# Laser-Driver.net
KiCad netlist of a schematic drawn in EAGLE
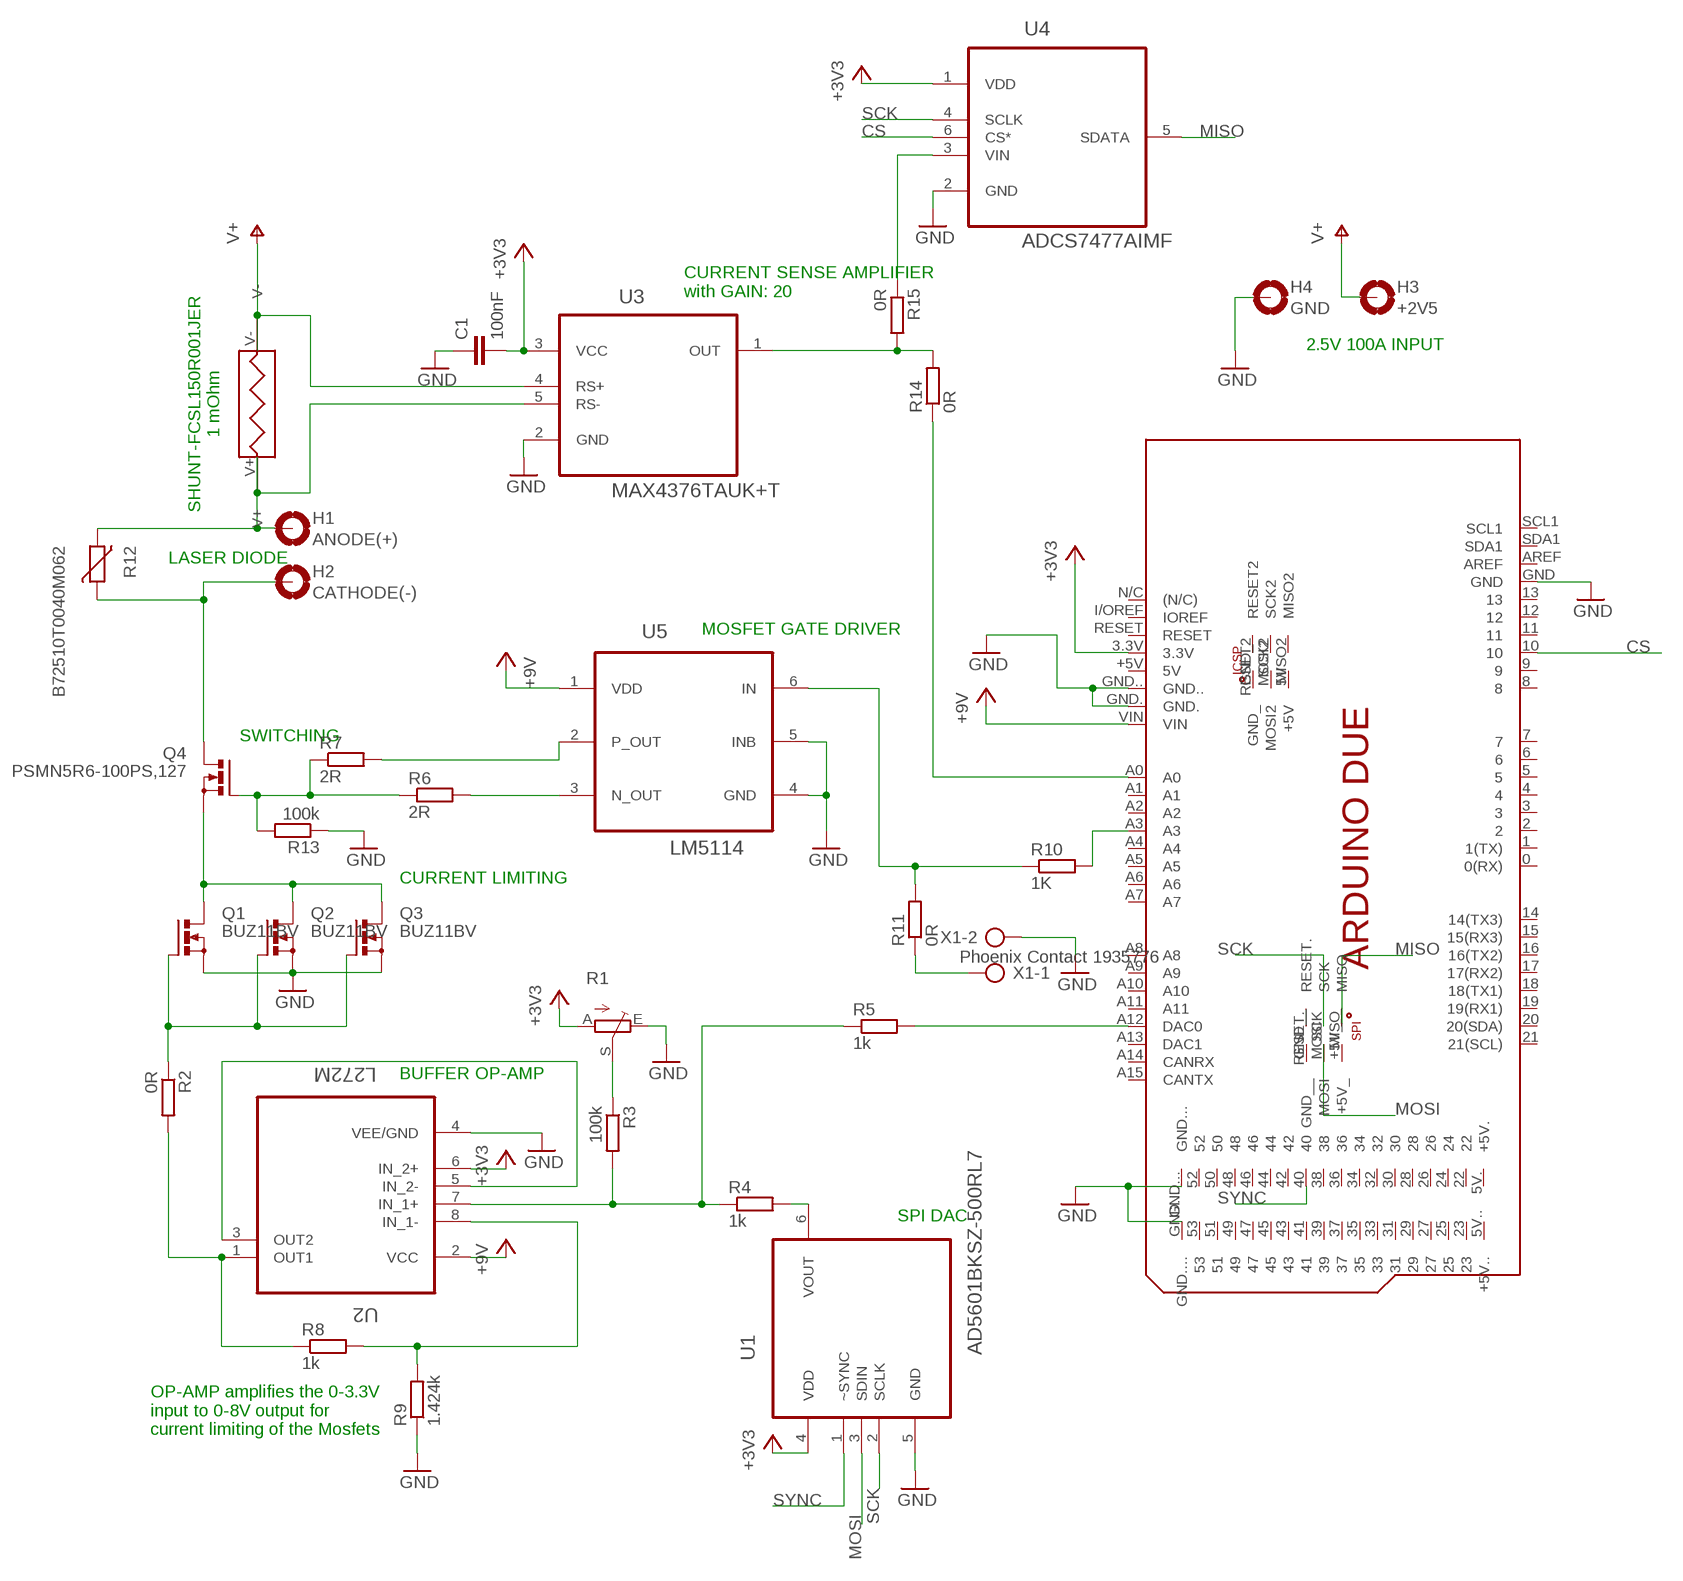
[diagram p0: schematic, sheet 1]

(export (version "E")
  (design (tool "Eeschema 10.0.6"))
  (components
    (comp (ref "C1")
      (value "100nF")
      (footprint "eagle-import:C0805")
      (libsource (lib "eagle-import") (part "C-EUC0805"))
    )
    (comp (ref "H1")
      (value "ANODE(+)")
      (footprint "eagle-import:3,2-PAD")
      (libsource (lib "eagle-import") (part "MOUNT-PAD-ROUND3.2"))
    )
    (comp (ref "H2")
      (value "CATHODE(-)")
      (footprint "eagle-import:3,2-PAD")
      (libsource (lib "eagle-import") (part "MOUNT-PAD-ROUND3.2"))
    )
    (comp (ref "H3")
      (value "+2V5")
      (footprint "eagle-import:3,2-PAD")
      (libsource (lib "eagle-import") (part "MOUNT-PAD-ROUND3.2"))
    )
    (comp (ref "H4")
      (value "GND")
      (footprint "eagle-import:3,2-PAD")
      (libsource (lib "eagle-import") (part "MOUNT-PAD-ROUND3.2"))
    )
    (comp (ref "PCB1")
      (value "ARDUINO_DUE_SHIELD_SPI")
      (footprint "eagle-import:ARDUINO_DUE_SHIELD_SPI")
      (libsource (lib "eagle-import") (part "ARDUINO_DUE_SHIELD_SPI"))
    )
    (comp (ref "Q1")
      (value "BUZ11BV")
      (footprint "eagle-import:TO220BV")
      (libsource (lib "eagle-import") (part "BUZ11BV"))
    )
    (comp (ref "Q2")
      (value "BUZ11BV")
      (footprint "eagle-import:TO220BV")
      (libsource (lib "eagle-import") (part "BUZ11BV"))
    )
    (comp (ref "Q3")
      (value "BUZ11BV")
      (footprint "eagle-import:TO220BV")
      (libsource (lib "eagle-import") (part "BUZ11BV"))
    )
    (comp (ref "Q4")
      (value "PSMN5R6-100PS,127")
      (footprint "eagle-import:TO220BV")
      (libsource (lib "eagle-import") (part "BUZ11BV"))
    )
    (comp (ref "R1")
      (value "TRIM_EU-B64W")
      (footprint "eagle-import:B64W")
      (libsource (lib "eagle-import") (part "TRIM_EU-B64W"))
    )
    (comp (ref "R2")
      (value "0R")
      (footprint "eagle-import:R0805")
      (libsource (lib "eagle-import") (part "R-EU_R0805"))
    )
    (comp (ref "R3")
      (value "100k")
      (footprint "eagle-import:R0805")
      (libsource (lib "eagle-import") (part "R-EU_R0805"))
    )
    (comp (ref "R4")
      (value "1k")
      (footprint "eagle-import:R0805")
      (libsource (lib "eagle-import") (part "R-EU_R0805"))
    )
    (comp (ref "R5")
      (value "1k")
      (footprint "eagle-import:R0805")
      (libsource (lib "eagle-import") (part "R-EU_R0805"))
    )
    (comp (ref "R6")
      (value "2R")
      (footprint "eagle-import:R0805")
      (libsource (lib "eagle-import") (part "R-EU_R0805"))
    )
    (comp (ref "R7")
      (value "2R")
      (footprint "eagle-import:R0805")
      (libsource (lib "eagle-import") (part "R-EU_R0805"))
    )
    (comp (ref "R8")
      (value "1k")
      (footprint "eagle-import:R0805")
      (libsource (lib "eagle-import") (part "R-EU_R0805"))
    )
    (comp (ref "R9")
      (value "1.424k")
      (footprint "eagle-import:R0805")
      (libsource (lib "eagle-import") (part "R-EU_R0805"))
    )
    (comp (ref "R10")
      (value "1K")
      (footprint "eagle-import:R0805")
      (libsource (lib "eagle-import") (part "R-EU_R0805"))
    )
    (comp (ref "R11")
      (value "0R")
      (footprint "eagle-import:R0805")
      (libsource (lib "eagle-import") (part "R-EU_R0805"))
    )
    (comp (ref "R12")
      (value "B72510T0040M062")
      (footprint "eagle-import:CT_CN0805")
      (libsource (lib "eagle-import") (part "VARISTORCN0805"))
    )
    (comp (ref "R13")
      (value "100k")
      (footprint "eagle-import:R0805")
      (libsource (lib "eagle-import") (part "R-EU_R0805"))
    )
    (comp (ref "R14")
      (value "0R")
      (footprint "eagle-import:R0805")
      (libsource (lib "eagle-import") (part "R-EU_R0805"))
    )
    (comp (ref "R15")
      (value "0R")
      (footprint "eagle-import:R0805")
      (libsource (lib "eagle-import") (part "R-EU_R0805"))
    )
    (comp (ref "U$1")
      (value "SHUNT-FCSL150R001-NOKELVIN")
      (footprint "eagle-import:SHUNT-FCSL150R001-NOKELVIN")
      (libsource (lib "eagle-import") (part "SHUNT-FCSL150R001-NOKELVIN"))
    )
    (comp (ref "U1")
      (value "AD5601BKSZ-500RL7")
      (footprint "eagle-import:SOT65P210X110-6N")
      (libsource (lib "eagle-import") (part "AD5601BKSZ-500RL7"))
    )
    (comp (ref "U2")
      (value "L272M")
      (footprint "eagle-import:DIP254P762X508-8")
      (libsource (lib "eagle-import") (part "L272M"))
    )
    (comp (ref "U3")
      (value "MAX4376TAUK+T")
      (footprint "eagle-import:SOT95P280X145-5N")
      (fields (field (name "MPN") "MAX4372TEUK+T"))
      (libsource (lib "eagle-import") (part "MAX4376"))
    )
    (comp (ref "U4")
      (value "ADCS7477AIMF")
      (footprint "eagle-import:SOT95P280X145-6N")
      (fields (field (name "MPN") "AD7477ARTZ-500RL7"))
      (libsource (lib "eagle-import") (part "AD7477ARTZ-500RL7"))
    )
    (comp (ref "U5")
      (value "LM5114")
      (footprint "eagle-import:SOT95P280X145-6N")
      (fields (field (name "MPN") "LM5114BMF/NOPB"))
      (libsource (lib "eagle-import") (part "LM5114"))
    )
    (comp (ref "X1")
      (value "Phoenix Contact 1935776")
      (footprint "eagle-import:AK500_2")
      (libsource (lib "eagle-import") (part "AK500/2"))
    )
  )
  (nets
    (net (code "1") (name "+3V3") (class "Default")
      (node (ref "C1") (pin "2") (pinfunction "2_2") (pintype "passive"))
      (node (ref "PCB1") (pin "3.3V") (pinfunction "3.3V_3.3V") (pintype "bidirectional"))
      (node (ref "R1") (pin "A") (pinfunction "A_A") (pintype "passive"))
      (node (ref "U1") (pin "4") (pinfunction "VDD_4") (pintype "power_in"))
      (node (ref "U2") (pin "6") (pinfunction "IN_2+_6") (pintype "input"))
      (node (ref "U3") (pin "3") (pinfunction "VCC_3") (pintype "power_in"))
      (node (ref "U4") (pin "1") (pinfunction "VDD_1") (pintype "power_in"))
    )
    (net (code "2") (name "+9V") (class "Default")
      (node (ref "PCB1") (pin "VIN") (pinfunction "VIN_VIN") (pintype "bidirectional"))
      (node (ref "U2") (pin "2") (pinfunction "VCC_2") (pintype "power_in"))
      (node (ref "U5") (pin "1") (pinfunction "VDD_1") (pintype "power_in"))
    )
    (net (code "3") (name "/CS") (class "Default")
      (node (ref "PCB1") (pin "10") (pinfunction "10_10") (pintype "bidirectional"))
      (node (ref "U4") (pin "6") (pinfunction "CS*_6") (pintype "passive"))
    )
    (net (code "4") (name "/MISO") (class "Default")
      (node (ref "PCB1") (pin "MISO") (pinfunction "MISO_MISO") (pintype "bidirectional"))
      (node (ref "U4") (pin "5") (pinfunction "SDATA_5") (pintype "passive"))
    )
    (net (code "5") (name "/MOSI") (class "Default")
      (node (ref "PCB1") (pin "MOSI") (pinfunction "MOSI_MOSI") (pintype "bidirectional"))
      (node (ref "U1") (pin "3") (pinfunction "SDIN_3") (pintype "input"))
    )
    (net (code "6") (name "/SCK") (class "Default")
      (node (ref "PCB1") (pin "SCK") (pinfunction "SCK_SCK") (pintype "bidirectional"))
      (node (ref "U1") (pin "2") (pinfunction "SCLK_2") (pintype "input"))
      (node (ref "U4") (pin "4") (pinfunction "SCLK_4") (pintype "passive"))
    )
    (net (code "7") (name "/SYNC") (class "Default")
      (node (ref "PCB1") (pin "40") (pinfunction "40_40") (pintype "bidirectional"))
      (node (ref "U1") (pin "1") (pinfunction "~{SYNC}_1") (pintype "input"))
    )
    (net (code "8") (name "GND") (class "Default")
      (node (ref "C1") (pin "1") (pinfunction "1_1") (pintype "passive"))
      (node (ref "H4") (pin "B3,2") (pinfunction "MOUNT_B3,2") (pintype "passive"))
      (node (ref "PCB1") (pin "GND") (pinfunction "GND_GND") (pintype "bidirectional"))
      (node (ref "PCB1") (pin "GND.") (pinfunction "GND._GND.") (pintype "bidirectional"))
      (node (ref "PCB1") (pin "GND..") (pinfunction "GND.._GND..") (pintype "bidirectional"))
      (node (ref "PCB1") (pin "GND...") (pinfunction "GND..._GND...") (pintype "bidirectional"))
      (node (ref "PCB1") (pin "GND....") (pinfunction "GND...._GND....") (pintype "bidirectional"))
      (node (ref "Q1") (pin "S") (pinfunction "S_S") (pintype "passive"))
      (node (ref "Q2") (pin "S") (pinfunction "S_S") (pintype "passive"))
      (node (ref "Q3") (pin "S") (pinfunction "S_S") (pintype "passive"))
      (node (ref "R1") (pin "E") (pinfunction "E_E") (pintype "passive"))
      (node (ref "R13") (pin "1") (pinfunction "1_1") (pintype "passive"))
      (node (ref "R9") (pin "1") (pinfunction "1_1") (pintype "passive"))
      (node (ref "U1") (pin "5") (pinfunction "GND_5") (pintype "passive"))
      (node (ref "U2") (pin "4") (pinfunction "VEE/GND_4") (pintype "power_in"))
      (node (ref "U3") (pin "2") (pinfunction "GND_2") (pintype "passive"))
      (node (ref "U4") (pin "2") (pinfunction "GND_2") (pintype "passive"))
      (node (ref "U5") (pin "4") (pinfunction "GND_4") (pintype "passive"))
      (node (ref "U5") (pin "5") (pinfunction "INB_5") (pintype "input"))
      (node (ref "X1") (pin "2") (pinfunction "KL_2") (pintype "passive"))
    )
    (net (code "9") (name "Net-(H1-MOUNT)") (class "Default")
      (node (ref "H1") (pin "B3,2") (pinfunction "MOUNT_B3,2") (pintype "passive"))
      (node (ref "R12") (pin "2") (pinfunction "2_2") (pintype "passive"))
      (node (ref "U$1") (pin "V+") (pinfunction "V+_V+") (pintype "bidirectional"))
      (node (ref "U3") (pin "5") (pinfunction "RS-_5") (pintype "passive"))
    )
    (net (code "10") (name "Net-(H2-MOUNT)") (class "Default")
      (node (ref "H2") (pin "B3,2") (pinfunction "MOUNT_B3,2") (pintype "passive"))
      (node (ref "Q4") (pin "D") (pinfunction "D_D") (pintype "passive"))
      (node (ref "R12") (pin "1") (pinfunction "1_1") (pintype "passive"))
    )
    (net (code "11") (name "Net-(PCB1-DAC0)") (class "Default")
      (node (ref "PCB1") (pin "A12") (pinfunction "DAC0_A12") (pintype "bidirectional"))
      (node (ref "R5") (pin "2") (pinfunction "2_2") (pintype "passive"))
    )
    (net (code "12") (name "Net-(PCB1-PadA0)") (class "Default")
      (node (ref "PCB1") (pin "A0") (pinfunction "A0_A0") (pintype "bidirectional"))
      (node (ref "R14") (pin "1") (pinfunction "1_1") (pintype "passive"))
    )
    (net (code "13") (name "Net-(PCB1-PadA3)") (class "Default")
      (node (ref "PCB1") (pin "A3") (pinfunction "A3_A3") (pintype "bidirectional"))
      (node (ref "R10") (pin "2") (pinfunction "2_2") (pintype "passive"))
    )
    (net (code "14") (name "Net-(Q1-PadD)") (class "Default")
      (node (ref "Q1") (pin "D") (pinfunction "D_D") (pintype "passive"))
      (node (ref "Q2") (pin "D") (pinfunction "D_D") (pintype "passive"))
      (node (ref "Q3") (pin "D") (pinfunction "D_D") (pintype "passive"))
      (node (ref "Q4") (pin "S") (pinfunction "S_S") (pintype "passive"))
    )
    (net (code "15") (name "Net-(Q1-PadG)") (class "Default")
      (node (ref "Q1") (pin "G") (pinfunction "G_G") (pintype "passive"))
      (node (ref "Q2") (pin "G") (pinfunction "G_G") (pintype "passive"))
      (node (ref "Q3") (pin "G") (pinfunction "G_G") (pintype "passive"))
      (node (ref "R2") (pin "1") (pinfunction "1_1") (pintype "passive"))
    )
    (net (code "16") (name "Net-(Q4-PadG)") (class "Default")
      (node (ref "Q4") (pin "G") (pinfunction "G_G") (pintype "passive"))
      (node (ref "R13") (pin "2") (pinfunction "2_2") (pintype "passive"))
      (node (ref "R6") (pin "1") (pinfunction "1_1") (pintype "passive"))
      (node (ref "R7") (pin "1") (pinfunction "1_1") (pintype "passive"))
    )
    (net (code "17") (name "Net-(R1-PadS)") (class "Default")
      (node (ref "R1") (pin "S") (pinfunction "S_S") (pintype "passive"))
      (node (ref "R3") (pin "1") (pinfunction "1_1") (pintype "passive"))
    )
    (net (code "18") (name "Net-(U1-VOUT)") (class "Default")
      (node (ref "R4") (pin "2") (pinfunction "2_2") (pintype "passive"))
      (node (ref "U1") (pin "6") (pinfunction "VOUT_6") (pintype "output"))
    )
    (net (code "19") (name "Net-(U2-IN_1+)") (class "Default")
      (node (ref "R3") (pin "2") (pinfunction "2_2") (pintype "passive"))
      (node (ref "R4") (pin "1") (pinfunction "1_1") (pintype "passive"))
      (node (ref "R5") (pin "1") (pinfunction "1_1") (pintype "passive"))
      (node (ref "U2") (pin "7") (pinfunction "IN_1+_7") (pintype "input"))
    )
    (net (code "20") (name "Net-(U2-IN_1-)") (class "Default")
      (node (ref "R8") (pin "2") (pinfunction "2_2") (pintype "passive"))
      (node (ref "R9") (pin "2") (pinfunction "2_2") (pintype "passive"))
      (node (ref "U2") (pin "8") (pinfunction "IN_1-_8") (pintype "input"))
    )
    (net (code "21") (name "Net-(U2-IN_2-)") (class "Default")
      (node (ref "U2") (pin "3") (pinfunction "OUT2_3") (pintype "output"))
      (node (ref "U2") (pin "5") (pinfunction "IN_2-_5") (pintype "input"))
    )
    (net (code "22") (name "Net-(U2-OUT1)") (class "Default")
      (node (ref "R2") (pin "2") (pinfunction "2_2") (pintype "passive"))
      (node (ref "R8") (pin "1") (pinfunction "1_1") (pintype "passive"))
      (node (ref "U2") (pin "1") (pinfunction "OUT1_1") (pintype "output"))
    )
    (net (code "23") (name "Net-(U3-OUT)") (class "Default")
      (node (ref "R14") (pin "2") (pinfunction "2_2") (pintype "passive"))
      (node (ref "R15") (pin "2") (pinfunction "2_2") (pintype "passive"))
      (node (ref "U3") (pin "1") (pinfunction "OUT_1") (pintype "output"))
    )
    (net (code "24") (name "Net-(U4-VIN)") (class "Default")
      (node (ref "R15") (pin "1") (pinfunction "1_1") (pintype "passive"))
      (node (ref "U4") (pin "3") (pinfunction "VIN_3") (pintype "passive"))
    )
    (net (code "25") (name "Net-(U5-IN)") (class "Default")
      (node (ref "R10") (pin "1") (pinfunction "1_1") (pintype "passive"))
      (node (ref "R11") (pin "2") (pinfunction "2_2") (pintype "passive"))
      (node (ref "U5") (pin "6") (pinfunction "IN_6") (pintype "input"))
    )
    (net (code "26") (name "Net-(U5-N_OUT)") (class "Default")
      (node (ref "R6") (pin "2") (pinfunction "2_2") (pintype "passive"))
      (node (ref "U5") (pin "3") (pinfunction "N_OUT_3") (pintype "output"))
    )
    (net (code "27") (name "Net-(U5-P_OUT)") (class "Default")
      (node (ref "R7") (pin "2") (pinfunction "2_2") (pintype "passive"))
      (node (ref "U5") (pin "2") (pinfunction "P_OUT_2") (pintype "output"))
    )
    (net (code "28") (name "Net-(X1A-KL)") (class "Default")
      (node (ref "R11") (pin "1") (pinfunction "1_1") (pintype "passive"))
      (node (ref "X1") (pin "1") (pinfunction "KL_1") (pintype "passive"))
    )
    (net (code "29") (name "V+") (class "Default")
      (node (ref "H3") (pin "B3,2") (pinfunction "MOUNT_B3,2") (pintype "passive"))
      (node (ref "U$1") (pin "V-") (pinfunction "V-_V-") (pintype "bidirectional"))
      (node (ref "U3") (pin "4") (pinfunction "RS+_4") (pintype "passive"))
    )
    (net (code "30") (name "unconnected-(PCB1-(N{slash}C)-PadN{slash}C)") (class "Default")
      (node (ref "PCB1") (pin "N/C") (pinfunction "(N/C)_N/C") (pintype "bidirectional"))
    )
    (net (code "31") (name "unconnected-(PCB1-+5V-Pad5V)") (class "Default")
      (node (ref "PCB1") (pin "5V") (pinfunction "+5V_5V") (pintype "bidirectional"))
    )
    (net (code "32") (name "unconnected-(PCB1-+5V.-Pad5V.)") (class "Default")
      (node (ref "PCB1") (pin "5V.") (pinfunction "+5V._5V.") (pintype "bidirectional"))
    )
    (net (code "33") (name "unconnected-(PCB1-+5V..-Pad5V..)") (class "Default")
      (node (ref "PCB1") (pin "5V..") (pinfunction "+5V.._5V..") (pintype "bidirectional"))
    )
    (net (code "34") (name "unconnected-(PCB1-0(RX)-Pad0)") (class "Default")
      (node (ref "PCB1") (pin "0") (pinfunction "0(RX)_0") (pintype "bidirectional"))
    )
    (net (code "35") (name "unconnected-(PCB1-1(TX)-Pad1)") (class "Default")
      (node (ref "PCB1") (pin "1") (pinfunction "1(TX)_1") (pintype "bidirectional"))
    )
    (net (code "36") (name "unconnected-(PCB1-5V-Pad+5V)") (class "Default")
      (node (ref "PCB1") (pin "+5V") (pinfunction "5V_+5V") (pintype "bidirectional"))
    )
    (net (code "37") (name "unconnected-(PCB1-14(TX3)-Pad14)") (class "Default")
      (node (ref "PCB1") (pin "14") (pinfunction "14(TX3)_14") (pintype "bidirectional"))
    )
    (net (code "38") (name "unconnected-(PCB1-15(RX3)-Pad15)") (class "Default")
      (node (ref "PCB1") (pin "15") (pinfunction "15(RX3)_15") (pintype "bidirectional"))
    )
    (net (code "39") (name "unconnected-(PCB1-16(TX2)-Pad16)") (class "Default")
      (node (ref "PCB1") (pin "16") (pinfunction "16(TX2)_16") (pintype "bidirectional"))
    )
    (net (code "40") (name "unconnected-(PCB1-17(RX2)-Pad17)") (class "Default")
      (node (ref "PCB1") (pin "17") (pinfunction "17(RX2)_17") (pintype "bidirectional"))
    )
    (net (code "41") (name "unconnected-(PCB1-18(TX1)-Pad18)") (class "Default")
      (node (ref "PCB1") (pin "18") (pinfunction "18(TX1)_18") (pintype "bidirectional"))
    )
    (net (code "42") (name "unconnected-(PCB1-19(RX1)-Pad19)") (class "Default")
      (node (ref "PCB1") (pin "19") (pinfunction "19(RX1)_19") (pintype "bidirectional"))
    )
    (net (code "43") (name "unconnected-(PCB1-20(SDA)-Pad20)") (class "Default")
      (node (ref "PCB1") (pin "20") (pinfunction "20(SDA)_20") (pintype "bidirectional"))
    )
    (net (code "44") (name "unconnected-(PCB1-21(SCL)-Pad21)") (class "Default")
      (node (ref "PCB1") (pin "21") (pinfunction "21(SCL)_21") (pintype "bidirectional"))
    )
    (net (code "45") (name "unconnected-(PCB1-CANRX-PadA14)") (class "Default")
      (node (ref "PCB1") (pin "A14") (pinfunction "CANRX_A14") (pintype "bidirectional"))
    )
    (net (code "46") (name "unconnected-(PCB1-CANTX-PadA15)") (class "Default")
      (node (ref "PCB1") (pin "A15") (pinfunction "CANTX_A15") (pintype "bidirectional"))
    )
    (net (code "47") (name "unconnected-(PCB1-DAC1-PadA13)") (class "Default")
      (node (ref "PCB1") (pin "A13") (pinfunction "DAC1_A13") (pintype "bidirectional"))
    )
    (net (code "48") (name "unconnected-(PCB1-IOREF-PadI{slash}OREF)") (class "Default")
      (node (ref "PCB1") (pin "I/OREF") (pinfunction "IOREF_I/OREF") (pintype "bidirectional"))
    )
    (net (code "49") (name "unconnected-(PCB1-Pad+5V_)") (class "Default")
      (node (ref "PCB1") (pin "+5V_") (pinfunction "+5V__+5V_") (pintype "bidirectional"))
    )
    (net (code "50") (name "unconnected-(PCB1-Pad2)") (class "Default")
      (node (ref "PCB1") (pin "2") (pinfunction "2_2") (pintype "bidirectional"))
    )
    (net (code "51") (name "unconnected-(PCB1-Pad3)") (class "Default")
      (node (ref "PCB1") (pin "3") (pinfunction "3_3") (pintype "bidirectional"))
    )
    (net (code "52") (name "unconnected-(PCB1-Pad4)") (class "Default")
      (node (ref "PCB1") (pin "4") (pinfunction "4_4") (pintype "bidirectional"))
    )
    (net (code "53") (name "unconnected-(PCB1-Pad5)") (class "Default")
      (node (ref "PCB1") (pin "5") (pinfunction "5_5") (pintype "bidirectional"))
    )
    (net (code "54") (name "unconnected-(PCB1-Pad6)") (class "Default")
      (node (ref "PCB1") (pin "6") (pinfunction "6_6") (pintype "bidirectional"))
    )
    (net (code "55") (name "unconnected-(PCB1-Pad7)") (class "Default")
      (node (ref "PCB1") (pin "7") (pinfunction "7_7") (pintype "bidirectional"))
    )
    (net (code "56") (name "unconnected-(PCB1-Pad8)") (class "Default")
      (node (ref "PCB1") (pin "8") (pinfunction "8_8") (pintype "bidirectional"))
    )
    (net (code "57") (name "unconnected-(PCB1-Pad9)") (class "Default")
      (node (ref "PCB1") (pin "9") (pinfunction "9_9") (pintype "bidirectional"))
    )
    (net (code "58") (name "unconnected-(PCB1-Pad11)") (class "Default")
      (node (ref "PCB1") (pin "11") (pinfunction "11_11") (pintype "bidirectional"))
    )
    (net (code "59") (name "unconnected-(PCB1-Pad12)") (class "Default")
      (node (ref "PCB1") (pin "12") (pinfunction "12_12") (pintype "bidirectional"))
    )
    (net (code "60") (name "unconnected-(PCB1-Pad13)") (class "Default")
      (node (ref "PCB1") (pin "13") (pinfunction "13_13") (pintype "bidirectional"))
    )
    (net (code "61") (name "unconnected-(PCB1-Pad22)") (class "Default")
      (node (ref "PCB1") (pin "22") (pinfunction "22_22") (pintype "bidirectional"))
    )
    (net (code "62") (name "unconnected-(PCB1-Pad23)") (class "Default")
      (node (ref "PCB1") (pin "23") (pinfunction "23_23") (pintype "bidirectional"))
    )
    (net (code "63") (name "unconnected-(PCB1-Pad24)") (class "Default")
      (node (ref "PCB1") (pin "24") (pinfunction "24_24") (pintype "bidirectional"))
    )
    (net (code "64") (name "unconnected-(PCB1-Pad25)") (class "Default")
      (node (ref "PCB1") (pin "25") (pinfunction "25_25") (pintype "bidirectional"))
    )
    (net (code "65") (name "unconnected-(PCB1-Pad26)") (class "Default")
      (node (ref "PCB1") (pin "26") (pinfunction "26_26") (pintype "bidirectional"))
    )
    (net (code "66") (name "unconnected-(PCB1-Pad27)") (class "Default")
      (node (ref "PCB1") (pin "27") (pinfunction "27_27") (pintype "bidirectional"))
    )
    (net (code "67") (name "unconnected-(PCB1-Pad28)") (class "Default")
      (node (ref "PCB1") (pin "28") (pinfunction "28_28") (pintype "bidirectional"))
    )
    (net (code "68") (name "unconnected-(PCB1-Pad29)") (class "Default")
      (node (ref "PCB1") (pin "29") (pinfunction "29_29") (pintype "bidirectional"))
    )
    (net (code "69") (name "unconnected-(PCB1-Pad30)") (class "Default")
      (node (ref "PCB1") (pin "30") (pinfunction "30_30") (pintype "bidirectional"))
    )
    (net (code "70") (name "unconnected-(PCB1-Pad31)") (class "Default")
      (node (ref "PCB1") (pin "31") (pinfunction "31_31") (pintype "bidirectional"))
    )
    (net (code "71") (name "unconnected-(PCB1-Pad32)") (class "Default")
      (node (ref "PCB1") (pin "32") (pinfunction "32_32") (pintype "bidirectional"))
    )
    (net (code "72") (name "unconnected-(PCB1-Pad33)") (class "Default")
      (node (ref "PCB1") (pin "33") (pinfunction "33_33") (pintype "bidirectional"))
    )
    (net (code "73") (name "unconnected-(PCB1-Pad34)") (class "Default")
      (node (ref "PCB1") (pin "34") (pinfunction "34_34") (pintype "bidirectional"))
    )
    (net (code "74") (name "unconnected-(PCB1-Pad35)") (class "Default")
      (node (ref "PCB1") (pin "35") (pinfunction "35_35") (pintype "bidirectional"))
    )
    (net (code "75") (name "unconnected-(PCB1-Pad36)") (class "Default")
      (node (ref "PCB1") (pin "36") (pinfunction "36_36") (pintype "bidirectional"))
    )
    (net (code "76") (name "unconnected-(PCB1-Pad37)") (class "Default")
      (node (ref "PCB1") (pin "37") (pinfunction "37_37") (pintype "bidirectional"))
    )
    (net (code "77") (name "unconnected-(PCB1-Pad38)") (class "Default")
      (node (ref "PCB1") (pin "38") (pinfunction "38_38") (pintype "bidirectional"))
    )
    (net (code "78") (name "unconnected-(PCB1-Pad39)") (class "Default")
      (node (ref "PCB1") (pin "39") (pinfunction "39_39") (pintype "bidirectional"))
    )
    (net (code "79") (name "unconnected-(PCB1-Pad41)") (class "Default")
      (node (ref "PCB1") (pin "41") (pinfunction "41_41") (pintype "bidirectional"))
    )
    (net (code "80") (name "unconnected-(PCB1-Pad42)") (class "Default")
      (node (ref "PCB1") (pin "42") (pinfunction "42_42") (pintype "bidirectional"))
    )
    (net (code "81") (name "unconnected-(PCB1-Pad43)") (class "Default")
      (node (ref "PCB1") (pin "43") (pinfunction "43_43") (pintype "bidirectional"))
    )
    (net (code "82") (name "unconnected-(PCB1-Pad44)") (class "Default")
      (node (ref "PCB1") (pin "44") (pinfunction "44_44") (pintype "bidirectional"))
    )
    (net (code "83") (name "unconnected-(PCB1-Pad45)") (class "Default")
      (node (ref "PCB1") (pin "45") (pinfunction "45_45") (pintype "bidirectional"))
    )
    (net (code "84") (name "unconnected-(PCB1-Pad46)") (class "Default")
      (node (ref "PCB1") (pin "46") (pinfunction "46_46") (pintype "bidirectional"))
    )
    (net (code "85") (name "unconnected-(PCB1-Pad47)") (class "Default")
      (node (ref "PCB1") (pin "47") (pinfunction "47_47") (pintype "bidirectional"))
    )
    (net (code "86") (name "unconnected-(PCB1-Pad48)") (class "Default")
      (node (ref "PCB1") (pin "48") (pinfunction "48_48") (pintype "bidirectional"))
    )
    (net (code "87") (name "unconnected-(PCB1-Pad49)") (class "Default")
      (node (ref "PCB1") (pin "49") (pinfunction "49_49") (pintype "bidirectional"))
    )
    (net (code "88") (name "unconnected-(PCB1-Pad50)") (class "Default")
      (node (ref "PCB1") (pin "50") (pinfunction "50_50") (pintype "bidirectional"))
    )
    (net (code "89") (name "unconnected-(PCB1-Pad51)") (class "Default")
      (node (ref "PCB1") (pin "51") (pinfunction "51_51") (pintype "bidirectional"))
    )
    (net (code "90") (name "unconnected-(PCB1-Pad52)") (class "Default")
      (node (ref "PCB1") (pin "52") (pinfunction "52_52") (pintype "bidirectional"))
    )
    (net (code "91") (name "unconnected-(PCB1-Pad53)") (class "Default")
      (node (ref "PCB1") (pin "53") (pinfunction "53_53") (pintype "bidirectional"))
    )
    (net (code "92") (name "unconnected-(PCB1-PadA1)") (class "Default")
      (node (ref "PCB1") (pin "A1") (pinfunction "A1_A1") (pintype "bidirectional"))
    )
    (net (code "93") (name "unconnected-(PCB1-PadA2)") (class "Default")
      (node (ref "PCB1") (pin "A2") (pinfunction "A2_A2") (pintype "bidirectional"))
    )
    (net (code "94") (name "unconnected-(PCB1-PadA4)") (class "Default")
      (node (ref "PCB1") (pin "A4") (pinfunction "A4_A4") (pintype "bidirectional"))
    )
    (net (code "95") (name "unconnected-(PCB1-PadA5)") (class "Default")
      (node (ref "PCB1") (pin "A5") (pinfunction "A5_A5") (pintype "bidirectional"))
    )
    (net (code "96") (name "unconnected-(PCB1-PadA6)") (class "Default")
      (node (ref "PCB1") (pin "A6") (pinfunction "A6_A6") (pintype "bidirectional"))
    )
    (net (code "97") (name "unconnected-(PCB1-PadA7)") (class "Default")
      (node (ref "PCB1") (pin "A7") (pinfunction "A7_A7") (pintype "bidirectional"))
    )
    (net (code "98") (name "unconnected-(PCB1-PadA8)") (class "Default")
      (node (ref "PCB1") (pin "A8") (pinfunction "A8_A8") (pintype "bidirectional"))
    )
    (net (code "99") (name "unconnected-(PCB1-PadA9)") (class "Default")
      (node (ref "PCB1") (pin "A9") (pinfunction "A9_A9") (pintype "bidirectional"))
    )
    (net (code "100") (name "unconnected-(PCB1-PadA10)") (class "Default")
      (node (ref "PCB1") (pin "A10") (pinfunction "A10_A10") (pintype "bidirectional"))
    )
    (net (code "101") (name "unconnected-(PCB1-PadA11)") (class "Default")
      (node (ref "PCB1") (pin "A11") (pinfunction "A11_A11") (pintype "bidirectional"))
    )
    (net (code "102") (name "unconnected-(PCB1-PadAREF)") (class "Default")
      (node (ref "PCB1") (pin "AREF") (pinfunction "AREF_AREF") (pintype "bidirectional"))
    )
    (net (code "103") (name "unconnected-(PCB1-PadGND_)") (class "Default")
      (node (ref "PCB1") (pin "GND_") (pinfunction "GND__GND_") (pintype "bidirectional"))
    )
    (net (code "104") (name "unconnected-(PCB1-PadGND__)") (class "Default")
      (node (ref "PCB1") (pin "GND__") (pinfunction "GND___GND__") (pintype "bidirectional"))
    )
    (net (code "105") (name "unconnected-(PCB1-PadMISO2)") (class "Default")
      (node (ref "PCB1") (pin "MISO2") (pinfunction "MISO2_MISO2") (pintype "bidirectional"))
    )
    (net (code "106") (name "unconnected-(PCB1-PadMOSI2)") (class "Default")
      (node (ref "PCB1") (pin "MOSI2") (pinfunction "MOSI2_MOSI2") (pintype "bidirectional"))
    )
    (net (code "107") (name "unconnected-(PCB1-PadRESET)") (class "Default")
      (node (ref "PCB1") (pin "RESET") (pinfunction "RESET_RESET") (pintype "bidirectional"))
    )
    (net (code "108") (name "unconnected-(PCB1-PadRESET.)") (class "Default")
      (node (ref "PCB1") (pin "RESET.") (pinfunction "RESET._RESET.") (pintype "bidirectional"))
    )
    (net (code "109") (name "unconnected-(PCB1-PadRESET2)") (class "Default")
      (node (ref "PCB1") (pin "RESET2") (pinfunction "RESET2_RESET2") (pintype "bidirectional"))
    )
    (net (code "110") (name "unconnected-(PCB1-PadSCK2)") (class "Default")
      (node (ref "PCB1") (pin "SCK2") (pinfunction "SCK2_SCK2") (pintype "bidirectional"))
    )
    (net (code "111") (name "unconnected-(PCB1-PadSCL1)") (class "Default")
      (node (ref "PCB1") (pin "SCL1") (pinfunction "SCL1_SCL1") (pintype "bidirectional"))
    )
    (net (code "112") (name "unconnected-(PCB1-PadSDA1)") (class "Default")
      (node (ref "PCB1") (pin "SDA1") (pinfunction "SDA1_SDA1") (pintype "bidirectional"))
    )
  )
)
